# Seguidor.net
KiCad netlist of a schematic drawn in EAGLE
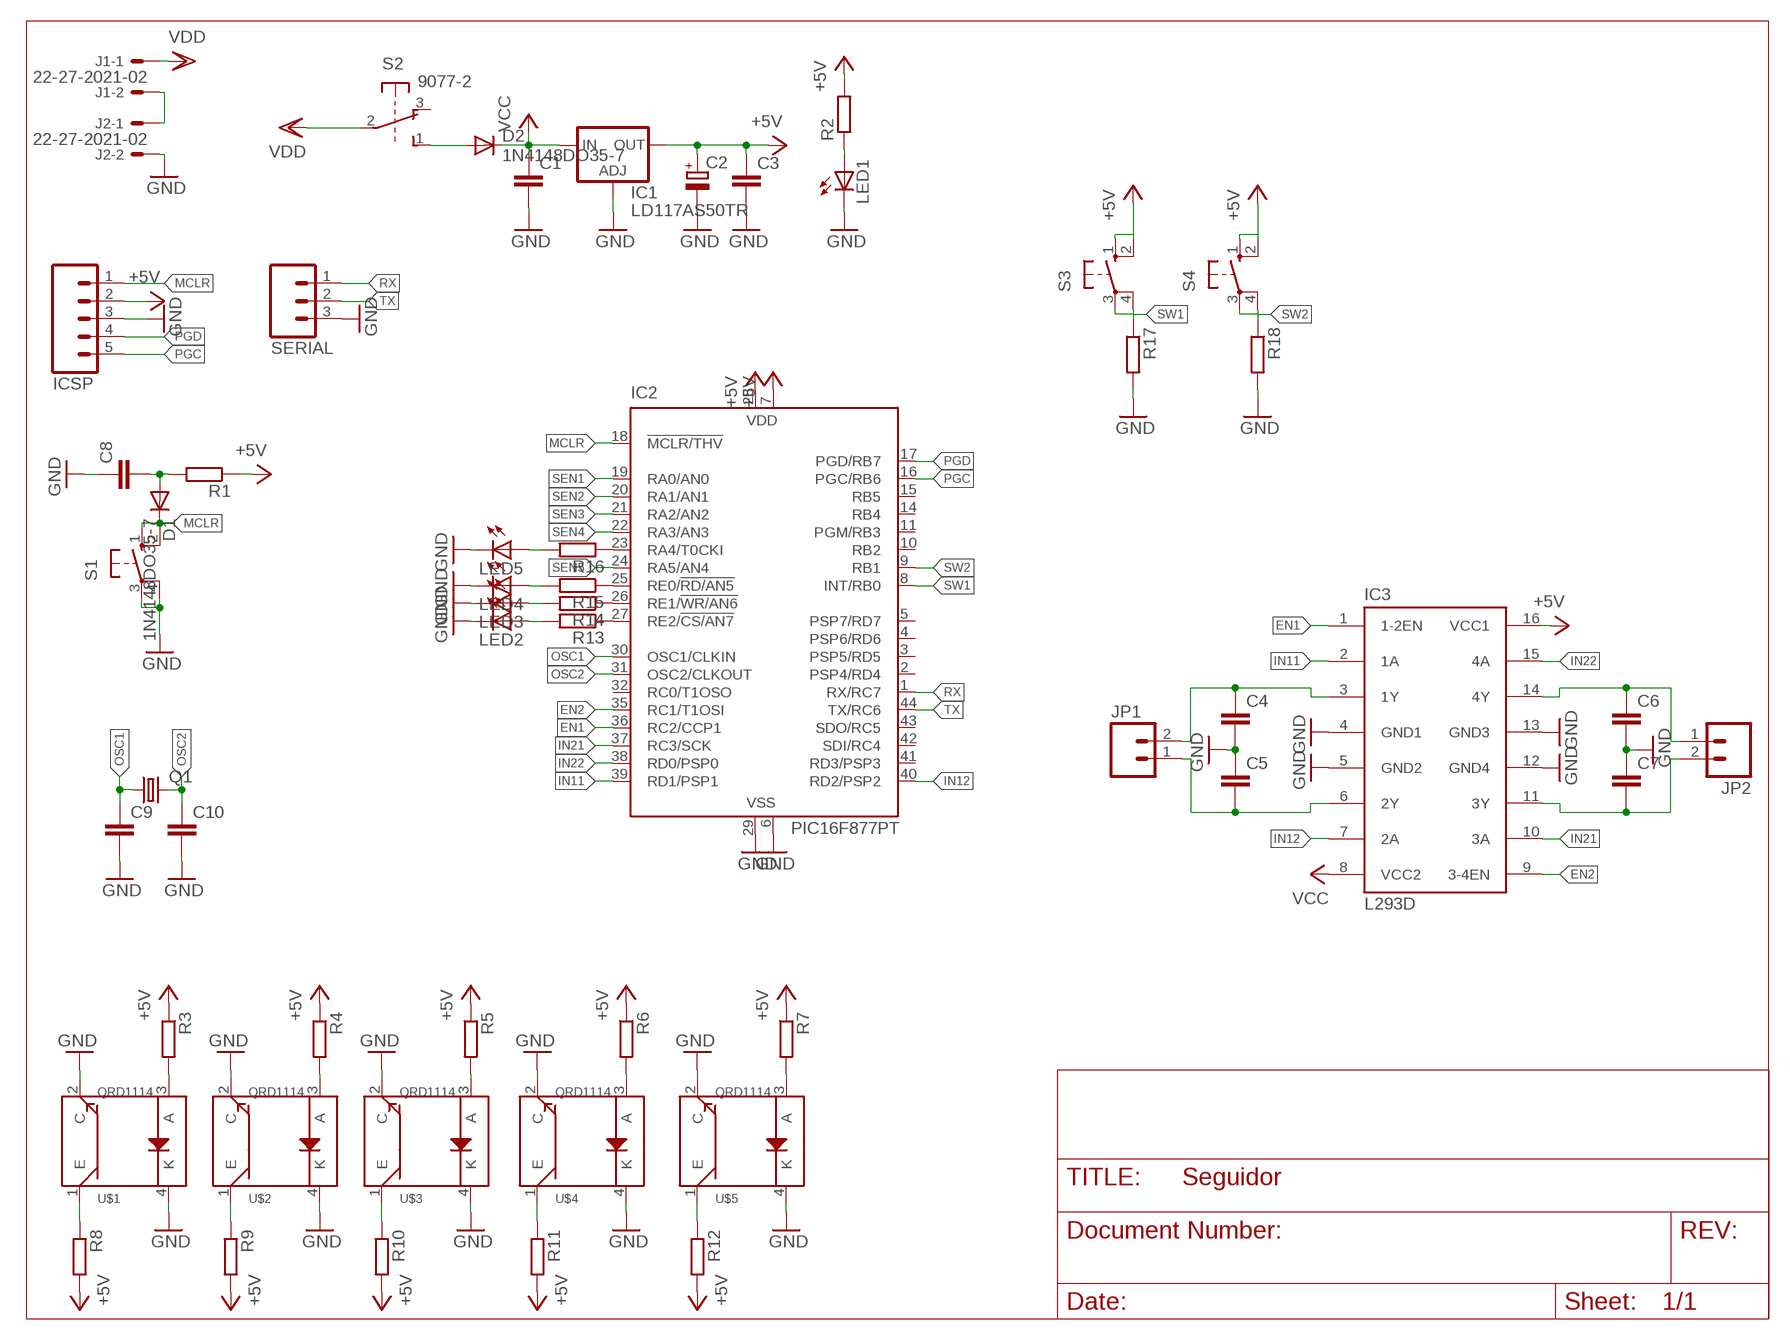
[diagram p0: schematic, sheet 1]

(export (version "E")
  (design (tool "Eeschema 10.0.6"))
  (components
    (comp (ref "C1")
      (value "C-EU050-024X044")
      (footprint "eagle-import:C050-024X044")
      (libsource (lib "eagle-import") (part "C-EU050-024X044"))
    )
    (comp (ref "C2")
      (value "CPOL-EU153CLV-0405")
      (footprint "eagle-import:153CLV-0405")
      (libsource (lib "eagle-import") (part "CPOL-EU153CLV-0405"))
    )
    (comp (ref "C3")
      (value "C-EU050-024X044")
      (footprint "eagle-import:C050-024X044")
      (libsource (lib "eagle-import") (part "C-EU050-024X044"))
    )
    (comp (ref "C4")
      (value "C-EU050-024X044")
      (footprint "eagle-import:C050-024X044")
      (libsource (lib "eagle-import") (part "C-EU050-024X044"))
    )
    (comp (ref "C5")
      (value "C-EU050-024X044")
      (footprint "eagle-import:C050-024X044")
      (libsource (lib "eagle-import") (part "C-EU050-024X044"))
    )
    (comp (ref "C6")
      (value "C-EU050-024X044")
      (footprint "eagle-import:C050-024X044")
      (libsource (lib "eagle-import") (part "C-EU050-024X044"))
    )
    (comp (ref "C7")
      (value "C-EU050-024X044")
      (footprint "eagle-import:C050-024X044")
      (libsource (lib "eagle-import") (part "C-EU050-024X044"))
    )
    (comp (ref "C8")
      (value "C-EU050-024X044")
      (footprint "eagle-import:C050-024X044")
      (libsource (lib "eagle-import") (part "C-EU050-024X044"))
    )
    (comp (ref "C9")
      (value "C-EU050-024X044")
      (footprint "eagle-import:C050-024X044")
      (libsource (lib "eagle-import") (part "C-EU050-024X044"))
    )
    (comp (ref "C10")
      (value "C-EU050-024X044")
      (footprint "eagle-import:C050-024X044")
      (libsource (lib "eagle-import") (part "C-EU050-024X044"))
    )
    (comp (ref "D1")
      (value "1N4148DO35-7")
      (footprint "eagle-import:DO35-7")
      (libsource (lib "eagle-import") (part "1N4148DO35-7"))
    )
    (comp (ref "D2")
      (value "1N4148DO35-7")
      (footprint "eagle-import:DO35-7")
      (libsource (lib "eagle-import") (part "1N4148DO35-7"))
    )
    (comp (ref "IC1")
      (value "LD117AS50TR")
      (footprint "eagle-import:SOT223")
      (libsource (lib "eagle-import") (part "LD117A?S50TR"))
    )
    (comp (ref "IC2")
      (value "PIC16F877PT")
      (footprint "eagle-import:TQFP44")
      (fields (field (name "MF") "MICROCHIP") (field (name "MPN") "PIC16F877-04/PQ"))
      (libsource (lib "eagle-import") (part "PIC16F87PT7"))
    )
    (comp (ref "IC3")
      (value "L293D")
      (footprint "eagle-import:DIL16")
      (libsource (lib "eagle-import") (part "L293D"))
    )
    (comp (ref "ICSP")
      (value "M05PTH_LONGPADS")
      (footprint "eagle-import:1X05_LONGPADS")
      (libsource (lib "eagle-import") (part "M05PTH_LONGPADS"))
    )
    (comp (ref "J1")
      (value "22-27-2021-02")
      (footprint "eagle-import:6410-02")
      (libsource (lib "eagle-import") (part "22-?-0227-2021"))
    )
    (comp (ref "J2")
      (value "22-27-2021-02")
      (footprint "eagle-import:6410-02")
      (libsource (lib "eagle-import") (part "22-?-0227-2021"))
    )
    (comp (ref "JP1")
      (value "M02")
      (footprint "eagle-import:1X02_LONGPADS")
      (libsource (lib "eagle-import") (part "M02"))
    )
    (comp (ref "JP2")
      (value "M02")
      (footprint "eagle-import:1X02_LONGPADS")
      (libsource (lib "eagle-import") (part "M02"))
    )
    (comp (ref "LED1")
      (value "LED3MM")
      (footprint "eagle-import:LED3MM")
      (libsource (lib "eagle-import") (part "LED3MM"))
    )
    (comp (ref "LED2")
      (value "LED3MM")
      (footprint "eagle-import:LED3MM")
      (libsource (lib "eagle-import") (part "LED3MM"))
    )
    (comp (ref "LED3")
      (value "LED3MM")
      (footprint "eagle-import:LED3MM")
      (libsource (lib "eagle-import") (part "LED3MM"))
    )
    (comp (ref "LED4")
      (value "LED3MM")
      (footprint "eagle-import:LED3MM")
      (libsource (lib "eagle-import") (part "LED3MM"))
    )
    (comp (ref "LED5")
      (value "LED3MM")
      (footprint "eagle-import:LED3MM")
      (libsource (lib "eagle-import") (part "LED3MM"))
    )
    (comp (ref "Q1")
      (value "CRYSTALHC49UP")
      (footprint "eagle-import:HC49UP")
      (fields (field (name "OC_FARNELL") "unknown"))
      (libsource (lib "eagle-import") (part "CRYSTALHC49UP"))
    )
    (comp (ref "R1")
      (value "R-EU_0207/7")
      (footprint "eagle-import:0207_7")
      (libsource (lib "eagle-import") (part "R-EU_0207/7"))
    )
    (comp (ref "R2")
      (value "R-EU_0207/7")
      (footprint "eagle-import:0207_7")
      (libsource (lib "eagle-import") (part "R-EU_0207/7"))
    )
    (comp (ref "R3")
      (value "R-EU_0207/7")
      (footprint "eagle-import:0207_7")
      (libsource (lib "eagle-import") (part "R-EU_0207/7"))
    )
    (comp (ref "R4")
      (value "R-EU_0207/7")
      (footprint "eagle-import:0207_7")
      (libsource (lib "eagle-import") (part "R-EU_0207/7"))
    )
    (comp (ref "R5")
      (value "R-EU_0207/7")
      (footprint "eagle-import:0207_7")
      (libsource (lib "eagle-import") (part "R-EU_0207/7"))
    )
    (comp (ref "R6")
      (value "R-EU_0207/7")
      (footprint "eagle-import:0207_7")
      (libsource (lib "eagle-import") (part "R-EU_0207/7"))
    )
    (comp (ref "R7")
      (value "R-EU_0207/7")
      (footprint "eagle-import:0207_7")
      (libsource (lib "eagle-import") (part "R-EU_0207/7"))
    )
    (comp (ref "R8")
      (value "R-EU_0207/7")
      (footprint "eagle-import:0207_7")
      (libsource (lib "eagle-import") (part "R-EU_0207/7"))
    )
    (comp (ref "R9")
      (value "R-EU_0207/7")
      (footprint "eagle-import:0207_7")
      (libsource (lib "eagle-import") (part "R-EU_0207/7"))
    )
    (comp (ref "R10")
      (value "R-EU_0207/7")
      (footprint "eagle-import:0207_7")
      (libsource (lib "eagle-import") (part "R-EU_0207/7"))
    )
    (comp (ref "R11")
      (value "R-EU_0207/7")
      (footprint "eagle-import:0207_7")
      (libsource (lib "eagle-import") (part "R-EU_0207/7"))
    )
    (comp (ref "R12")
      (value "R-EU_0207/7")
      (footprint "eagle-import:0207_7")
      (libsource (lib "eagle-import") (part "R-EU_0207/7"))
    )
    (comp (ref "R13")
      (value "R-EU_0207/7")
      (footprint "eagle-import:0207_7")
      (libsource (lib "eagle-import") (part "R-EU_0207/7"))
    )
    (comp (ref "R14")
      (value "R-EU_0207/7")
      (footprint "eagle-import:0207_7")
      (libsource (lib "eagle-import") (part "R-EU_0207/7"))
    )
    (comp (ref "R15")
      (value "R-EU_0207/7")
      (footprint "eagle-import:0207_7")
      (libsource (lib "eagle-import") (part "R-EU_0207/7"))
    )
    (comp (ref "R16")
      (value "R-EU_0207/7")
      (footprint "eagle-import:0207_7")
      (libsource (lib "eagle-import") (part "R-EU_0207/7"))
    )
    (comp (ref "R17")
      (value "R-EU_0207/7")
      (footprint "eagle-import:0207_7")
      (libsource (lib "eagle-import") (part "R-EU_0207/7"))
    )
    (comp (ref "R18")
      (value "R-EU_0207/7")
      (footprint "eagle-import:0207_7")
      (libsource (lib "eagle-import") (part "R-EU_0207/7"))
    )
    (comp (ref "S1")
      (value "10-XX")
      (footprint "eagle-import:B3F-10XX")
      (fields (field (name "MPN") "B3F-1000"))
      (libsource (lib "eagle-import") (part "10-XX"))
    )
    (comp (ref "S2")
      (value "9077-2")
      (footprint "eagle-import:9077-2")
      (libsource (lib "eagle-import") (part "9077-2"))
    )
    (comp (ref "S3")
      (value "10-XX")
      (footprint "eagle-import:B3F-10XX")
      (fields
        (field (name "MPN") "B3F-1000")
        (field (name "MPN_1") "B3F-1000")
        (field (name "OC_FARNELL") "176432")
        (field (name "OC_NEWARK") "36M3542")
      )
      (libsource (lib "eagle-import") (part "10-XX"))
    )
    (comp (ref "S4")
      (value "10-XX")
      (footprint "eagle-import:B3F-10XX")
      (fields
        (field (name "MPN") "B3F-1000")
        (field (name "MPN_1") "B3F-1000")
        (field (name "OC_FARNELL") "176432")
        (field (name "OC_NEWARK") "36M3542")
      )
      (libsource (lib "eagle-import") (part "10-XX"))
    )
    (comp (ref "SERIAL")
      (value "M03LOCK_LONGPADS")
      (footprint "eagle-import:1X03_LOCK_LONGPADS")
      (libsource (lib "eagle-import") (part "M03LOCK_LONGPADS"))
    )
    (comp (ref "U$1")
      (value "QRD1114")
      (footprint "eagle-import:QRD1114")
      (libsource (lib "eagle-import") (part "QRD1114"))
    )
    (comp (ref "U$2")
      (value "QRD1114")
      (footprint "eagle-import:QRD1114")
      (libsource (lib "eagle-import") (part "QRD1114"))
    )
    (comp (ref "U$3")
      (value "QRD1114")
      (footprint "eagle-import:QRD1114")
      (libsource (lib "eagle-import") (part "QRD1114"))
    )
    (comp (ref "U$4")
      (value "QRD1114")
      (footprint "eagle-import:QRD1114")
      (libsource (lib "eagle-import") (part "QRD1114"))
    )
    (comp (ref "U$5")
      (value "QRD1114")
      (footprint "eagle-import:QRD1114")
      (libsource (lib "eagle-import") (part "QRD1114"))
    )
  )
  (nets
    (net (code "1") (name "+5V") (class "Default")
      (node (ref "C2") (pin "+") (pinfunction "+_+") (pintype "passive"))
      (node (ref "C3") (pin "1") (pinfunction "1_1") (pintype "passive"))
      (node (ref "IC1") (pin "4") (pinfunction "OUT_4") (pintype "passive"))
      (node (ref "IC2") (pin "28") (pinfunction "VDD_28") (pintype "power_in"))
      (node (ref "IC2") (pin "7") (pinfunction "VDD_7") (pintype "power_in"))
      (node (ref "IC3") (pin "16") (pinfunction "VCC1_16") (pintype "power_in"))
      (node (ref "ICSP") (pin "2") (pinfunction "2_2") (pintype "passive"))
      (node (ref "R1") (pin "1") (pinfunction "1_1") (pintype "passive"))
      (node (ref "R10") (pin "2") (pinfunction "2_2") (pintype "passive"))
      (node (ref "R11") (pin "2") (pinfunction "2_2") (pintype "passive"))
      (node (ref "R12") (pin "2") (pinfunction "2_2") (pintype "passive"))
      (node (ref "R2") (pin "2") (pinfunction "2_2") (pintype "passive"))
      (node (ref "R3") (pin "1") (pinfunction "1_1") (pintype "passive"))
      (node (ref "R4") (pin "1") (pinfunction "1_1") (pintype "passive"))
      (node (ref "R5") (pin "1") (pinfunction "1_1") (pintype "passive"))
      (node (ref "R6") (pin "1") (pinfunction "1_1") (pintype "passive"))
      (node (ref "R7") (pin "1") (pinfunction "1_1") (pintype "passive"))
      (node (ref "R8") (pin "2") (pinfunction "2_2") (pintype "passive"))
      (node (ref "R9") (pin "2") (pinfunction "2_2") (pintype "passive"))
      (node (ref "S3") (pin "1") (pinfunction "S_1") (pintype "passive"))
      (node (ref "S3") (pin "2") (pinfunction "S1_2") (pintype "passive"))
      (node (ref "S4") (pin "1") (pinfunction "S_1") (pintype "passive"))
      (node (ref "S4") (pin "2") (pinfunction "S1_2") (pintype "passive"))
    )
    (net (code "2") (name "EN1") (class "Default")
      (node (ref "IC2") (pin "36") (pinfunction "RC2/CCP1_36") (pintype "bidirectional"))
      (node (ref "IC3") (pin "1") (pinfunction "1-2EN_1") (pintype "input"))
    )
    (net (code "3") (name "EN2") (class "Default")
      (node (ref "IC2") (pin "35") (pinfunction "RC1/T1OSI_35") (pintype "bidirectional"))
      (node (ref "IC3") (pin "9") (pinfunction "3-4EN_9") (pintype "input"))
    )
    (net (code "4") (name "GND") (class "Default")
      (node (ref "C1") (pin "2") (pinfunction "2_2") (pintype "passive"))
      (node (ref "C10") (pin "2") (pinfunction "2_2") (pintype "passive"))
      (node (ref "C2") (pin "-") (pinfunction "-_-") (pintype "passive"))
      (node (ref "C3") (pin "2") (pinfunction "2_2") (pintype "passive"))
      (node (ref "C4") (pin "2") (pinfunction "2_2") (pintype "passive"))
      (node (ref "C5") (pin "1") (pinfunction "1_1") (pintype "passive"))
      (node (ref "C6") (pin "2") (pinfunction "2_2") (pintype "passive"))
      (node (ref "C7") (pin "1") (pinfunction "1_1") (pintype "passive"))
      (node (ref "C8") (pin "1") (pinfunction "1_1") (pintype "passive"))
      (node (ref "C9") (pin "2") (pinfunction "2_2") (pintype "passive"))
      (node (ref "IC1") (pin "1") (pinfunction "ADJ_1") (pintype "input"))
      (node (ref "IC2") (pin "29") (pinfunction "VSS_29") (pintype "power_in"))
      (node (ref "IC2") (pin "6") (pinfunction "VSS_6") (pintype "power_in"))
      (node (ref "IC3") (pin "12") (pinfunction "GND4_12") (pintype "power_in"))
      (node (ref "IC3") (pin "13") (pinfunction "GND3_13") (pintype "power_in"))
      (node (ref "IC3") (pin "4") (pinfunction "GND1_4") (pintype "power_in"))
      (node (ref "IC3") (pin "5") (pinfunction "GND2_5") (pintype "power_in"))
      (node (ref "ICSP") (pin "3") (pinfunction "3_3") (pintype "passive"))
      (node (ref "J2") (pin "2") (pinfunction "S_2") (pintype "passive"))
      (node (ref "LED1") (pin "K") (pinfunction "C_K") (pintype "passive"))
      (node (ref "LED2") (pin "K") (pinfunction "C_K") (pintype "passive"))
      (node (ref "LED3") (pin "K") (pinfunction "C_K") (pintype "passive"))
      (node (ref "LED4") (pin "K") (pinfunction "C_K") (pintype "passive"))
      (node (ref "LED5") (pin "K") (pinfunction "C_K") (pintype "passive"))
      (node (ref "R17") (pin "2") (pinfunction "2_2") (pintype "passive"))
      (node (ref "R18") (pin "2") (pinfunction "2_2") (pintype "passive"))
      (node (ref "S1") (pin "3") (pinfunction "P_3") (pintype "passive"))
      (node (ref "S1") (pin "4") (pinfunction "P1_4") (pintype "passive"))
      (node (ref "SERIAL") (pin "3") (pinfunction "3_3") (pintype "passive"))
      (node (ref "U$1") (pin "2") (pinfunction "C_2") (pintype "bidirectional"))
      (node (ref "U$1") (pin "4") (pinfunction "K_4") (pintype "bidirectional"))
      (node (ref "U$2") (pin "2") (pinfunction "C_2") (pintype "bidirectional"))
      (node (ref "U$2") (pin "4") (pinfunction "K_4") (pintype "bidirectional"))
      (node (ref "U$3") (pin "2") (pinfunction "C_2") (pintype "bidirectional"))
      (node (ref "U$3") (pin "4") (pinfunction "K_4") (pintype "bidirectional"))
      (node (ref "U$4") (pin "2") (pinfunction "C_2") (pintype "bidirectional"))
      (node (ref "U$4") (pin "4") (pinfunction "K_4") (pintype "bidirectional"))
      (node (ref "U$5") (pin "2") (pinfunction "C_2") (pintype "bidirectional"))
      (node (ref "U$5") (pin "4") (pinfunction "K_4") (pintype "bidirectional"))
    )
    (net (code "5") (name "IN11") (class "Default")
      (node (ref "IC2") (pin "39") (pinfunction "RD1/PSP1_39") (pintype "bidirectional"))
      (node (ref "IC3") (pin "2") (pinfunction "1A_2") (pintype "input"))
    )
    (net (code "6") (name "IN12") (class "Default")
      (node (ref "IC2") (pin "40") (pinfunction "RD2/PSP2_40") (pintype "bidirectional"))
      (node (ref "IC3") (pin "7") (pinfunction "2A_7") (pintype "input"))
    )
    (net (code "7") (name "IN21") (class "Default")
      (node (ref "IC2") (pin "37") (pinfunction "RC3/SCK_37") (pintype "bidirectional"))
      (node (ref "IC3") (pin "10") (pinfunction "3A_10") (pintype "input"))
    )
    (net (code "8") (name "IN22") (class "Default")
      (node (ref "IC2") (pin "38") (pinfunction "RD0/PSP0_38") (pintype "bidirectional"))
      (node (ref "IC3") (pin "15") (pinfunction "4A_15") (pintype "input"))
    )
    (net (code "9") (name "MCLR") (class "Default")
      (node (ref "D1") (pin "C") (pinfunction "C_C") (pintype "passive"))
      (node (ref "IC2") (pin "18") (pinfunction "~{MCLR/THV}_18") (pintype "input"))
      (node (ref "ICSP") (pin "1") (pinfunction "1_1") (pintype "passive"))
      (node (ref "S1") (pin "1") (pinfunction "S_1") (pintype "passive"))
      (node (ref "S1") (pin "2") (pinfunction "S1_2") (pintype "passive"))
    )
    (net (code "10") (name "Net-(C8-Pad2)") (class "Default")
      (node (ref "C8") (pin "2") (pinfunction "2_2") (pintype "passive"))
      (node (ref "D1") (pin "A") (pinfunction "A_A") (pintype "passive"))
      (node (ref "R1") (pin "2") (pinfunction "2_2") (pintype "passive"))
    )
    (net (code "11") (name "Net-(IC2-RA4{slash}T0CKI)") (class "Default")
      (node (ref "IC2") (pin "23") (pinfunction "RA4/T0CKI_23") (pintype "bidirectional"))
      (node (ref "R16") (pin "1") (pinfunction "1_1") (pintype "passive"))
    )
    (net (code "12") (name "Net-(IC2-RE0{slash}~{RD{slash}AN5})") (class "Default")
      (node (ref "IC2") (pin "25") (pinfunction "RE0/~{RD/AN5}_25") (pintype "bidirectional"))
      (node (ref "R15") (pin "1") (pinfunction "1_1") (pintype "passive"))
    )
    (net (code "13") (name "Net-(IC2-RE1{slash}~{WR{slash}AN6})") (class "Default")
      (node (ref "IC2") (pin "26") (pinfunction "RE1/~{WR/AN6}_26") (pintype "bidirectional"))
      (node (ref "R14") (pin "1") (pinfunction "1_1") (pintype "passive"))
    )
    (net (code "14") (name "Net-(IC2-RE2{slash}~{CS{slash}AN7})") (class "Default")
      (node (ref "IC2") (pin "27") (pinfunction "RE2/~{CS/AN7}_27") (pintype "bidirectional"))
      (node (ref "R13") (pin "1") (pinfunction "1_1") (pintype "passive"))
    )
    (net (code "15") (name "Net-(IC3-1Y)") (class "Default")
      (node (ref "C4") (pin "1") (pinfunction "1_1") (pintype "passive"))
      (node (ref "IC3") (pin "3") (pinfunction "1Y_3") (pintype "output"))
      (node (ref "JP1") (pin "2") (pinfunction "2_2") (pintype "passive"))
    )
    (net (code "16") (name "Net-(IC3-2Y)") (class "Default")
      (node (ref "C5") (pin "2") (pinfunction "2_2") (pintype "passive"))
      (node (ref "IC3") (pin "6") (pinfunction "2Y_6") (pintype "output"))
      (node (ref "JP1") (pin "1") (pinfunction "1_1") (pintype "passive"))
    )
    (net (code "17") (name "Net-(IC3-3Y)") (class "Default")
      (node (ref "C7") (pin "2") (pinfunction "2_2") (pintype "passive"))
      (node (ref "IC3") (pin "11") (pinfunction "3Y_11") (pintype "output"))
      (node (ref "JP2") (pin "2") (pinfunction "2_2") (pintype "passive"))
    )
    (net (code "18") (name "Net-(IC3-4Y)") (class "Default")
      (node (ref "C6") (pin "1") (pinfunction "1_1") (pintype "passive"))
      (node (ref "IC3") (pin "14") (pinfunction "4Y_14") (pintype "output"))
      (node (ref "JP2") (pin "1") (pinfunction "1_1") (pintype "passive"))
    )
    (net (code "19") (name "Net-(J1B-S)") (class "Default")
      (node (ref "J1") (pin "2") (pinfunction "S_2") (pintype "passive"))
      (node (ref "J2") (pin "1") (pinfunction "S_1") (pintype "passive"))
    )
    (net (code "20") (name "Net-(LED1-PadA)") (class "Default")
      (node (ref "LED1") (pin "A") (pinfunction "A_A") (pintype "passive"))
      (node (ref "R2") (pin "1") (pinfunction "1_1") (pintype "passive"))
    )
    (net (code "21") (name "Net-(LED2-PadA)") (class "Default")
      (node (ref "LED2") (pin "A") (pinfunction "A_A") (pintype "passive"))
      (node (ref "R13") (pin "2") (pinfunction "2_2") (pintype "passive"))
    )
    (net (code "22") (name "Net-(LED3-PadA)") (class "Default")
      (node (ref "LED3") (pin "A") (pinfunction "A_A") (pintype "passive"))
      (node (ref "R14") (pin "2") (pinfunction "2_2") (pintype "passive"))
    )
    (net (code "23") (name "Net-(LED4-PadA)") (class "Default")
      (node (ref "LED4") (pin "A") (pinfunction "A_A") (pintype "passive"))
      (node (ref "R15") (pin "2") (pinfunction "2_2") (pintype "passive"))
    )
    (net (code "24") (name "Net-(LED5-PadA)") (class "Default")
      (node (ref "LED5") (pin "A") (pinfunction "A_A") (pintype "passive"))
      (node (ref "R16") (pin "2") (pinfunction "2_2") (pintype "passive"))
    )
    (net (code "25") (name "Net-(S2A-S)") (class "Default")
      (node (ref "D2") (pin "A") (pinfunction "A_A") (pintype "passive"))
      (node (ref "S2") (pin "1") (pinfunction "S_1") (pintype "passive"))
    )
    (net (code "26") (name "Net-(U$1-A)") (class "Default")
      (node (ref "R3") (pin "2") (pinfunction "2_2") (pintype "passive"))
      (node (ref "U$1") (pin "3") (pinfunction "A_3") (pintype "bidirectional"))
    )
    (net (code "27") (name "Net-(U$2-A)") (class "Default")
      (node (ref "R4") (pin "2") (pinfunction "2_2") (pintype "passive"))
      (node (ref "U$2") (pin "3") (pinfunction "A_3") (pintype "bidirectional"))
    )
    (net (code "28") (name "Net-(U$3-A)") (class "Default")
      (node (ref "R5") (pin "2") (pinfunction "2_2") (pintype "passive"))
      (node (ref "U$3") (pin "3") (pinfunction "A_3") (pintype "bidirectional"))
    )
    (net (code "29") (name "Net-(U$4-A)") (class "Default")
      (node (ref "R6") (pin "2") (pinfunction "2_2") (pintype "passive"))
      (node (ref "U$4") (pin "3") (pinfunction "A_3") (pintype "bidirectional"))
    )
    (net (code "30") (name "Net-(U$5-A)") (class "Default")
      (node (ref "R7") (pin "2") (pinfunction "2_2") (pintype "passive"))
      (node (ref "U$5") (pin "3") (pinfunction "A_3") (pintype "bidirectional"))
    )
    (net (code "31") (name "OSC1") (class "Default")
      (node (ref "C9") (pin "1") (pinfunction "1_1") (pintype "passive"))
      (node (ref "IC2") (pin "30") (pinfunction "OSC1/CLKIN_30") (pintype "input"))
      (node (ref "Q1") (pin "1") (pinfunction "1_1") (pintype "passive"))
    )
    (net (code "32") (name "OSC2") (class "Default")
      (node (ref "C10") (pin "1") (pinfunction "1_1") (pintype "passive"))
      (node (ref "IC2") (pin "31") (pinfunction "OSC2/CLKOUT_31") (pintype "output"))
      (node (ref "Q1") (pin "2") (pinfunction "2_2") (pintype "passive"))
    )
    (net (code "33") (name "PGC") (class "Default")
      (node (ref "IC2") (pin "16") (pinfunction "PGC/RB6_16") (pintype "bidirectional"))
      (node (ref "ICSP") (pin "5") (pinfunction "5_5") (pintype "passive"))
    )
    (net (code "34") (name "PGD") (class "Default")
      (node (ref "IC2") (pin "17") (pinfunction "PGD/RB7_17") (pintype "bidirectional"))
      (node (ref "ICSP") (pin "4") (pinfunction "4_4") (pintype "passive"))
    )
    (net (code "35") (name "RX") (class "Default")
      (node (ref "IC2") (pin "1") (pinfunction "RX/RC7_1") (pintype "bidirectional"))
      (node (ref "SERIAL") (pin "1") (pinfunction "1_1") (pintype "passive"))
    )
    (net (code "36") (name "SEN1") (class "Default")
      (node (ref "IC2") (pin "19") (pinfunction "RA0/AN0_19") (pintype "bidirectional"))
      (node (ref "R8") (pin "1") (pinfunction "1_1") (pintype "passive"))
      (node (ref "U$1") (pin "1") (pinfunction "E_1") (pintype "bidirectional"))
    )
    (net (code "37") (name "SEN2") (class "Default")
      (node (ref "IC2") (pin "20") (pinfunction "RA1/AN1_20") (pintype "bidirectional"))
      (node (ref "R9") (pin "1") (pinfunction "1_1") (pintype "passive"))
      (node (ref "U$2") (pin "1") (pinfunction "E_1") (pintype "bidirectional"))
    )
    (net (code "38") (name "SEN3") (class "Default")
      (node (ref "IC2") (pin "21") (pinfunction "RA2/AN2_21") (pintype "bidirectional"))
      (node (ref "R10") (pin "1") (pinfunction "1_1") (pintype "passive"))
      (node (ref "U$3") (pin "1") (pinfunction "E_1") (pintype "bidirectional"))
    )
    (net (code "39") (name "SEN4") (class "Default")
      (node (ref "IC2") (pin "22") (pinfunction "RA3/AN3_22") (pintype "bidirectional"))
      (node (ref "R11") (pin "1") (pinfunction "1_1") (pintype "passive"))
      (node (ref "U$4") (pin "1") (pinfunction "E_1") (pintype "bidirectional"))
    )
    (net (code "40") (name "SEN5") (class "Default")
      (node (ref "IC2") (pin "24") (pinfunction "RA5/AN4_24") (pintype "bidirectional"))
      (node (ref "R12") (pin "1") (pinfunction "1_1") (pintype "passive"))
      (node (ref "U$5") (pin "1") (pinfunction "E_1") (pintype "bidirectional"))
    )
    (net (code "41") (name "SW1") (class "Default")
      (node (ref "IC2") (pin "8") (pinfunction "INT/RB0_8") (pintype "bidirectional"))
      (node (ref "R17") (pin "1") (pinfunction "1_1") (pintype "passive"))
      (node (ref "S3") (pin "3") (pinfunction "P_3") (pintype "passive"))
      (node (ref "S3") (pin "4") (pinfunction "P1_4") (pintype "passive"))
    )
    (net (code "42") (name "SW2") (class "Default")
      (node (ref "IC2") (pin "9") (pinfunction "RB1_9") (pintype "bidirectional"))
      (node (ref "R18") (pin "1") (pinfunction "1_1") (pintype "passive"))
      (node (ref "S4") (pin "3") (pinfunction "P_3") (pintype "passive"))
      (node (ref "S4") (pin "4") (pinfunction "P1_4") (pintype "passive"))
    )
    (net (code "43") (name "TX") (class "Default")
      (node (ref "IC2") (pin "44") (pinfunction "TX/RC6_44") (pintype "bidirectional"))
      (node (ref "SERIAL") (pin "2") (pinfunction "2_2") (pintype "passive"))
    )
    (net (code "44") (name "VCC") (class "Default")
      (node (ref "C1") (pin "1") (pinfunction "1_1") (pintype "passive"))
      (node (ref "D2") (pin "C") (pinfunction "C_C") (pintype "passive"))
      (node (ref "IC1") (pin "3") (pinfunction "IN_3") (pintype "input"))
      (node (ref "IC3") (pin "8") (pinfunction "VCC2_8") (pintype "power_in"))
    )
    (net (code "45") (name "VDD") (class "Default")
      (node (ref "J1") (pin "1") (pinfunction "S_1") (pintype "passive"))
      (node (ref "S2") (pin "2") (pinfunction "P_2") (pintype "passive"))
    )
    (net (code "46") (name "unconnected-(IC2-PGM{slash}RB3-Pad11)") (class "Default")
      (node (ref "IC2") (pin "11") (pinfunction "PGM/RB3_11") (pintype "bidirectional"))
    )
    (net (code "47") (name "unconnected-(IC2-PSP4{slash}RD4-Pad2)") (class "Default")
      (node (ref "IC2") (pin "2") (pinfunction "PSP4/RD4_2") (pintype "bidirectional"))
    )
    (net (code "48") (name "unconnected-(IC2-PSP5{slash}RD5-Pad3)") (class "Default")
      (node (ref "IC2") (pin "3") (pinfunction "PSP5/RD5_3") (pintype "bidirectional"))
    )
    (net (code "49") (name "unconnected-(IC2-PSP6{slash}RD6-Pad4)") (class "Default")
      (node (ref "IC2") (pin "4") (pinfunction "PSP6/RD6_4") (pintype "bidirectional"))
    )
    (net (code "50") (name "unconnected-(IC2-PSP7{slash}RD7-Pad5)") (class "Default")
      (node (ref "IC2") (pin "5") (pinfunction "PSP7/RD7_5") (pintype "bidirectional"))
    )
    (net (code "51") (name "unconnected-(IC2-RB2-Pad10)") (class "Default")
      (node (ref "IC2") (pin "10") (pinfunction "RB2_10") (pintype "bidirectional"))
    )
    (net (code "52") (name "unconnected-(IC2-RB4-Pad14)") (class "Default")
      (node (ref "IC2") (pin "14") (pinfunction "RB4_14") (pintype "bidirectional"))
    )
    (net (code "53") (name "unconnected-(IC2-RB5-Pad15)") (class "Default")
      (node (ref "IC2") (pin "15") (pinfunction "RB5_15") (pintype "bidirectional"))
    )
    (net (code "54") (name "unconnected-(IC2-RC0{slash}T1OSO-Pad32)") (class "Default")
      (node (ref "IC2") (pin "32") (pinfunction "RC0/T1OSO_32") (pintype "bidirectional"))
    )
    (net (code "55") (name "unconnected-(IC2-RD3{slash}PSP3-Pad41)") (class "Default")
      (node (ref "IC2") (pin "41") (pinfunction "RD3/PSP3_41") (pintype "bidirectional"))
    )
    (net (code "56") (name "unconnected-(IC2-SDI{slash}RC4-Pad42)") (class "Default")
      (node (ref "IC2") (pin "42") (pinfunction "SDI/RC4_42") (pintype "bidirectional"))
    )
    (net (code "57") (name "unconnected-(IC2-SDO{slash}RC5-Pad43)") (class "Default")
      (node (ref "IC2") (pin "43") (pinfunction "SDO/RC5_43") (pintype "bidirectional"))
    )
    (net (code "58") (name "unconnected-(S2A-O-Pad3)") (class "Default")
      (node (ref "S2") (pin "3") (pinfunction "O_3") (pintype "passive"))
    )
  )
)
